# IMU_Board.net
KiCad netlist of a schematic drawn in EAGLE
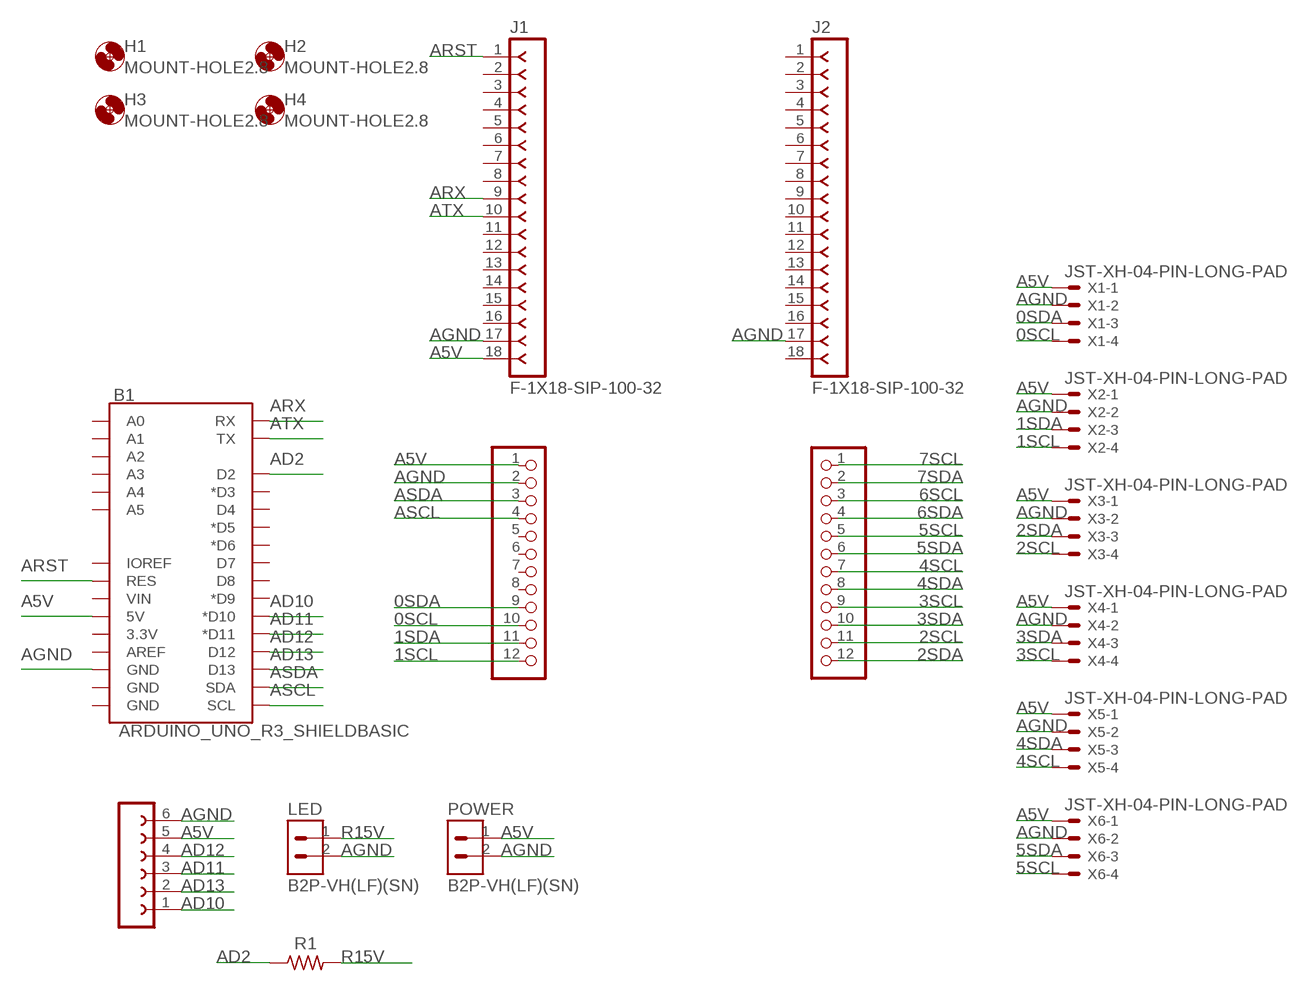
[diagram p0: schematic, sheet 1]

(export (version "E")
  (design (tool "Eeschema 10.0.6"))
  (components
    (comp (ref "B1")
      (value "ARDUINO_UNO_R3_SHIELDBASIC")
      (footprint "eagle-import:UNO_R3_SHIELD")
      (libsource (lib "eagle-import") (part "ARDUINO_UNO_R3_SHIELDBASIC"))
    )
    (comp (ref "H1")
      (value "MOUNT-HOLE2.8")
      (footprint "eagle-import:2,8")
      (libsource (lib "eagle-import") (part "MOUNT-HOLE2.8"))
    )
    (comp (ref "H2")
      (value "MOUNT-HOLE2.8")
      (footprint "eagle-import:2,8")
      (libsource (lib "eagle-import") (part "MOUNT-HOLE2.8"))
    )
    (comp (ref "H3")
      (value "MOUNT-HOLE2.8")
      (footprint "eagle-import:2,8")
      (libsource (lib "eagle-import") (part "MOUNT-HOLE2.8"))
    )
    (comp (ref "H4")
      (value "MOUNT-HOLE2.8")
      (footprint "eagle-import:2,8")
      (libsource (lib "eagle-import") (part "MOUNT-HOLE2.8"))
    )
    (comp (ref "J1")
      (value "F-1X18-SIP-100-32")
      (footprint "eagle-import:SIP-100-18-32")
      (libsource (lib "eagle-import") (part "F-1X18-SIP-100-32"))
    )
    (comp (ref "J2")
      (value "F-1X18-SIP-100-32")
      (footprint "eagle-import:SIP-100-18-32")
      (libsource (lib "eagle-import") (part "F-1X18-SIP-100-32"))
    )
    (comp (ref "JP1")
      (value "HEADER-1X12")
      (footprint "eagle-import:1X12_ROUND")
      (libsource (lib "eagle-import") (part "HEADER-1X12"))
    )
    (comp (ref "JP3")
      (value "HEADER-1X12")
      (footprint "eagle-import:1X12_ROUND")
      (libsource (lib "eagle-import") (part "HEADER-1X12"))
    )
    (comp (ref "LED")
      (value "B2P-VH(LF)(SN)")
      (footprint "eagle-import:HDR-02")
      (fields
        (field (name "DIGIKEY_PART_NUMBER") "455-1639-ND")
        (field (name "MANUFACTURER") "JST Sales America Inc.")
        (field (name "CREATED_BY") "PCBLayout.com")
      )
      (libsource (lib "eagle-import") (part "B2P-VH(LF)(SN)"))
    )
    (comp (ref "POWER")
      (value "B2P-VH(LF)(SN)")
      (footprint "eagle-import:HDR-02")
      (fields
        (field (name "DIGIKEY_PART_NUMBER") "455-1639-ND")
        (field (name "MANUFACTURER") "JST Sales America Inc.")
        (field (name "CREATED_BY") "PCBLayout.com")
      )
      (libsource (lib "eagle-import") (part "B2P-VH(LF)(SN)"))
    )
    (comp (ref "R1")
      (value "R-US_AXIAL-11.7MM-PITCH")
      (footprint "eagle-import:RESAD1176W63L850D250B")
      (libsource (lib "eagle-import") (part "R-USAXIAL-11.7MM-PITCH_"))
    )
    (comp (ref "SD")
      (value "FE06-1")
      (footprint "eagle-import:FE06")
      (libsource (lib "eagle-import") (part "FE06-1"))
    )
    (comp (ref "X1")
      (value "JST-XH-04-PIN-LONG-PAD")
      (footprint "eagle-import:JST-XH-04-PACKAGE-LONG-PAD")
      (libsource (lib "eagle-import") (part "JST-XH-04-PIN-LONG-PAD"))
    )
    (comp (ref "X2")
      (value "JST-XH-04-PIN-LONG-PAD")
      (footprint "eagle-import:JST-XH-04-PACKAGE-LONG-PAD")
      (libsource (lib "eagle-import") (part "JST-XH-04-PIN-LONG-PAD"))
    )
    (comp (ref "X3")
      (value "JST-XH-04-PIN-LONG-PAD")
      (footprint "eagle-import:JST-XH-04-PACKAGE-LONG-PAD")
      (libsource (lib "eagle-import") (part "JST-XH-04-PIN-LONG-PAD"))
    )
    (comp (ref "X4")
      (value "JST-XH-04-PIN-LONG-PAD")
      (footprint "eagle-import:JST-XH-04-PACKAGE-LONG-PAD")
      (libsource (lib "eagle-import") (part "JST-XH-04-PIN-LONG-PAD"))
    )
    (comp (ref "X5")
      (value "JST-XH-04-PIN-LONG-PAD")
      (footprint "eagle-import:JST-XH-04-PACKAGE-LONG-PAD")
      (libsource (lib "eagle-import") (part "JST-XH-04-PIN-LONG-PAD"))
    )
    (comp (ref "X6")
      (value "JST-XH-04-PIN-LONG-PAD")
      (footprint "eagle-import:JST-XH-04-PACKAGE-LONG-PAD")
      (libsource (lib "eagle-import") (part "JST-XH-04-PIN-LONG-PAD"))
    )
  )
  (nets
    (net (code "1") (name "/0SCL") (class "Default")
      (node (ref "JP3") (pin "10") (pinfunction "10_10") (pintype "passive"))
      (node (ref "X1") (pin "4") (pinfunction "S_4") (pintype "passive"))
    )
    (net (code "2") (name "/0SDA") (class "Default")
      (node (ref "JP3") (pin "9") (pinfunction "9_9") (pintype "passive"))
      (node (ref "X1") (pin "3") (pinfunction "S_3") (pintype "passive"))
    )
    (net (code "3") (name "/1SCL") (class "Default")
      (node (ref "JP3") (pin "12") (pinfunction "12_12") (pintype "passive"))
      (node (ref "X2") (pin "4") (pinfunction "S_4") (pintype "passive"))
    )
    (net (code "4") (name "/1SDA") (class "Default")
      (node (ref "JP3") (pin "11") (pinfunction "11_11") (pintype "passive"))
      (node (ref "X2") (pin "3") (pinfunction "S_3") (pintype "passive"))
    )
    (net (code "5") (name "/2SCL") (class "Default")
      (node (ref "JP1") (pin "11") (pinfunction "11_11") (pintype "passive"))
      (node (ref "X3") (pin "4") (pinfunction "S_4") (pintype "passive"))
    )
    (net (code "6") (name "/2SDA") (class "Default")
      (node (ref "JP1") (pin "12") (pinfunction "12_12") (pintype "passive"))
      (node (ref "X3") (pin "3") (pinfunction "S_3") (pintype "passive"))
    )
    (net (code "7") (name "/3SCL") (class "Default")
      (node (ref "JP1") (pin "9") (pinfunction "9_9") (pintype "passive"))
      (node (ref "X4") (pin "4") (pinfunction "S_4") (pintype "passive"))
    )
    (net (code "8") (name "/3SDA") (class "Default")
      (node (ref "JP1") (pin "10") (pinfunction "10_10") (pintype "passive"))
      (node (ref "X4") (pin "3") (pinfunction "S_3") (pintype "passive"))
    )
    (net (code "9") (name "/4SCL") (class "Default")
      (node (ref "JP1") (pin "7") (pinfunction "7_7") (pintype "passive"))
      (node (ref "X5") (pin "4") (pinfunction "S_4") (pintype "passive"))
    )
    (net (code "10") (name "/4SDA") (class "Default")
      (node (ref "JP1") (pin "8") (pinfunction "8_8") (pintype "passive"))
      (node (ref "X5") (pin "3") (pinfunction "S_3") (pintype "passive"))
    )
    (net (code "11") (name "/5SCL") (class "Default")
      (node (ref "JP1") (pin "5") (pinfunction "5_5") (pintype "passive"))
      (node (ref "X6") (pin "4") (pinfunction "S_4") (pintype "passive"))
    )
    (net (code "12") (name "/5SDA") (class "Default")
      (node (ref "JP1") (pin "6") (pinfunction "6_6") (pintype "passive"))
      (node (ref "X6") (pin "3") (pinfunction "S_3") (pintype "passive"))
    )
    (net (code "13") (name "/6SCL") (class "Default")
      (node (ref "JP1") (pin "3") (pinfunction "3_3") (pintype "passive"))
    )
    (net (code "14") (name "/6SDA") (class "Default")
      (node (ref "JP1") (pin "4") (pinfunction "4_4") (pintype "passive"))
    )
    (net (code "15") (name "/7SCL") (class "Default")
      (node (ref "JP1") (pin "1") (pinfunction "1_1") (pintype "passive"))
    )
    (net (code "16") (name "/7SDA") (class "Default")
      (node (ref "JP1") (pin "2") (pinfunction "2_2") (pintype "passive"))
    )
    (net (code "17") (name "/A5V") (class "Default")
      (node (ref "B1") (pin "5V") (pinfunction "5V_5V") (pintype "bidirectional"))
      (node (ref "J1") (pin "18") (pinfunction "18_18") (pintype "passive"))
      (node (ref "JP3") (pin "1") (pinfunction "1_1") (pintype "passive"))
      (node (ref "POWER") (pin "1") (pinfunction "1_1") (pintype "passive"))
      (node (ref "SD") (pin "5") (pinfunction "5_5") (pintype "passive"))
      (node (ref "X1") (pin "1") (pinfunction "S_1") (pintype "passive"))
      (node (ref "X2") (pin "1") (pinfunction "S_1") (pintype "passive"))
      (node (ref "X3") (pin "1") (pinfunction "S_1") (pintype "passive"))
      (node (ref "X4") (pin "1") (pinfunction "S_1") (pintype "passive"))
      (node (ref "X5") (pin "1") (pinfunction "S_1") (pintype "passive"))
      (node (ref "X6") (pin "1") (pinfunction "S_1") (pintype "passive"))
    )
    (net (code "18") (name "/AD2") (class "Default")
      (node (ref "B1") (pin "D2") (pinfunction "D2_D2") (pintype "bidirectional"))
      (node (ref "R1") (pin "1") (pinfunction "1_1") (pintype "passive"))
    )
    (net (code "19") (name "/AD10") (class "Default")
      (node (ref "B1") (pin "D10") (pinfunction "*D10_D10") (pintype "bidirectional"))
      (node (ref "SD") (pin "1") (pinfunction "1_1") (pintype "passive"))
    )
    (net (code "20") (name "/AD11") (class "Default")
      (node (ref "B1") (pin "D11") (pinfunction "*D11_D11") (pintype "bidirectional"))
      (node (ref "SD") (pin "3") (pinfunction "3_3") (pintype "passive"))
    )
    (net (code "21") (name "/AD12") (class "Default")
      (node (ref "B1") (pin "D12") (pinfunction "D12_D12") (pintype "bidirectional"))
      (node (ref "SD") (pin "4") (pinfunction "4_4") (pintype "passive"))
    )
    (net (code "22") (name "/AD13") (class "Default")
      (node (ref "B1") (pin "D13") (pinfunction "D13_D13") (pintype "bidirectional"))
      (node (ref "SD") (pin "2") (pinfunction "2_2") (pintype "passive"))
    )
    (net (code "23") (name "/AGND") (class "Default")
      (node (ref "B1") (pin "GND@2") (pinfunction "GND_GND@2") (pintype "bidirectional"))
      (node (ref "J1") (pin "17") (pinfunction "17_17") (pintype "passive"))
      (node (ref "J2") (pin "17") (pinfunction "17_17") (pintype "passive"))
      (node (ref "JP3") (pin "2") (pinfunction "2_2") (pintype "passive"))
      (node (ref "LED") (pin "2") (pinfunction "2_2") (pintype "passive"))
      (node (ref "POWER") (pin "2") (pinfunction "2_2") (pintype "passive"))
      (node (ref "SD") (pin "6") (pinfunction "6_6") (pintype "passive"))
      (node (ref "X1") (pin "2") (pinfunction "S_2") (pintype "passive"))
      (node (ref "X2") (pin "2") (pinfunction "S_2") (pintype "passive"))
      (node (ref "X3") (pin "2") (pinfunction "S_2") (pintype "passive"))
      (node (ref "X4") (pin "2") (pinfunction "S_2") (pintype "passive"))
      (node (ref "X5") (pin "2") (pinfunction "S_2") (pintype "passive"))
      (node (ref "X6") (pin "2") (pinfunction "S_2") (pintype "passive"))
    )
    (net (code "24") (name "/ARST") (class "Default")
      (node (ref "B1") (pin "RES") (pinfunction "RES_RES") (pintype "bidirectional"))
      (node (ref "J1") (pin "1") (pinfunction "1_1") (pintype "passive"))
    )
    (net (code "25") (name "/ARX") (class "Default")
      (node (ref "B1") (pin "RX") (pinfunction "RX_RX") (pintype "bidirectional"))
      (node (ref "J1") (pin "9") (pinfunction "9_9") (pintype "passive"))
    )
    (net (code "26") (name "/ASCL") (class "Default")
      (node (ref "B1") (pin "SCL") (pinfunction "SCL_SCL") (pintype "bidirectional"))
      (node (ref "JP3") (pin "4") (pinfunction "4_4") (pintype "passive"))
    )
    (net (code "27") (name "/ASDA") (class "Default")
      (node (ref "B1") (pin "SDA") (pinfunction "SDA_SDA") (pintype "bidirectional"))
      (node (ref "JP3") (pin "3") (pinfunction "3_3") (pintype "passive"))
    )
    (net (code "28") (name "/ATX") (class "Default")
      (node (ref "B1") (pin "TX") (pinfunction "TX_TX") (pintype "bidirectional"))
      (node (ref "J1") (pin "10") (pinfunction "10_10") (pintype "passive"))
    )
    (net (code "29") (name "/R15V") (class "Default")
      (node (ref "LED") (pin "1") (pinfunction "1_1") (pintype "passive"))
      (node (ref "R1") (pin "2") (pinfunction "2_2") (pintype "passive"))
    )
    (net (code "30") (name "unconnected-(B1-*D3-PadD3)") (class "Default")
      (node (ref "B1") (pin "D3") (pinfunction "*D3_D3") (pintype "bidirectional"))
    )
    (net (code "31") (name "unconnected-(B1-*D5-PadD5)") (class "Default")
      (node (ref "B1") (pin "D5") (pinfunction "*D5_D5") (pintype "bidirectional"))
    )
    (net (code "32") (name "unconnected-(B1-*D6-PadD6)") (class "Default")
      (node (ref "B1") (pin "D6") (pinfunction "*D6_D6") (pintype "bidirectional"))
    )
    (net (code "33") (name "unconnected-(B1-*D9-PadD9)") (class "Default")
      (node (ref "B1") (pin "D9") (pinfunction "*D9_D9") (pintype "bidirectional"))
    )
    (net (code "34") (name "unconnected-(B1-GND-PadGND@0)") (class "Default")
      (node (ref "B1") (pin "GND@0") (pinfunction "GND_GND@0") (pintype "bidirectional"))
    )
    (net (code "35") (name "unconnected-(B1-GND-PadGND@1)") (class "Default")
      (node (ref "B1") (pin "GND@1") (pinfunction "GND_GND@1") (pintype "bidirectional"))
    )
    (net (code "36") (name "unconnected-(B1-Pad3.3V)") (class "Default")
      (node (ref "B1") (pin "3.3V") (pinfunction "3.3V_3.3V") (pintype "bidirectional"))
    )
    (net (code "37") (name "unconnected-(B1-PadA0)") (class "Default")
      (node (ref "B1") (pin "A0") (pinfunction "A0_A0") (pintype "bidirectional"))
    )
    (net (code "38") (name "unconnected-(B1-PadA1)") (class "Default")
      (node (ref "B1") (pin "A1") (pinfunction "A1_A1") (pintype "bidirectional"))
    )
    (net (code "39") (name "unconnected-(B1-PadA2)") (class "Default")
      (node (ref "B1") (pin "A2") (pinfunction "A2_A2") (pintype "bidirectional"))
    )
    (net (code "40") (name "unconnected-(B1-PadA3)") (class "Default")
      (node (ref "B1") (pin "A3") (pinfunction "A3_A3") (pintype "bidirectional"))
    )
    (net (code "41") (name "unconnected-(B1-PadA4)") (class "Default")
      (node (ref "B1") (pin "A4") (pinfunction "A4_A4") (pintype "bidirectional"))
    )
    (net (code "42") (name "unconnected-(B1-PadA5)") (class "Default")
      (node (ref "B1") (pin "A5") (pinfunction "A5_A5") (pintype "bidirectional"))
    )
    (net (code "43") (name "unconnected-(B1-PadAREF)") (class "Default")
      (node (ref "B1") (pin "AREF") (pinfunction "AREF_AREF") (pintype "bidirectional"))
    )
    (net (code "44") (name "unconnected-(B1-PadD4)") (class "Default")
      (node (ref "B1") (pin "D4") (pinfunction "D4_D4") (pintype "bidirectional"))
    )
    (net (code "45") (name "unconnected-(B1-PadD7)") (class "Default")
      (node (ref "B1") (pin "D7") (pinfunction "D7_D7") (pintype "bidirectional"))
    )
    (net (code "46") (name "unconnected-(B1-PadD8)") (class "Default")
      (node (ref "B1") (pin "D8") (pinfunction "D8_D8") (pintype "bidirectional"))
    )
    (net (code "47") (name "unconnected-(B1-PadIOREF)") (class "Default")
      (node (ref "B1") (pin "IOREF") (pinfunction "IOREF_IOREF") (pintype "bidirectional"))
    )
    (net (code "48") (name "unconnected-(B1-PadVIN)") (class "Default")
      (node (ref "B1") (pin "VIN") (pinfunction "VIN_VIN") (pintype "bidirectional"))
    )
    (net (code "49") (name "unconnected-(J1-Pad2)") (class "Default")
      (node (ref "J1") (pin "2") (pinfunction "2_2") (pintype "passive"))
    )
    (net (code "50") (name "unconnected-(J1-Pad3)") (class "Default")
      (node (ref "J1") (pin "3") (pinfunction "3_3") (pintype "passive"))
    )
    (net (code "51") (name "unconnected-(J1-Pad4)") (class "Default")
      (node (ref "J1") (pin "4") (pinfunction "4_4") (pintype "passive"))
    )
    (net (code "52") (name "unconnected-(J1-Pad5)") (class "Default")
      (node (ref "J1") (pin "5") (pinfunction "5_5") (pintype "passive"))
    )
    (net (code "53") (name "unconnected-(J1-Pad6)") (class "Default")
      (node (ref "J1") (pin "6") (pinfunction "6_6") (pintype "passive"))
    )
    (net (code "54") (name "unconnected-(J1-Pad7)") (class "Default")
      (node (ref "J1") (pin "7") (pinfunction "7_7") (pintype "passive"))
    )
    (net (code "55") (name "unconnected-(J1-Pad8)") (class "Default")
      (node (ref "J1") (pin "8") (pinfunction "8_8") (pintype "passive"))
    )
    (net (code "56") (name "unconnected-(J1-Pad11)") (class "Default")
      (node (ref "J1") (pin "11") (pinfunction "11_11") (pintype "passive"))
    )
    (net (code "57") (name "unconnected-(J1-Pad12)") (class "Default")
      (node (ref "J1") (pin "12") (pinfunction "12_12") (pintype "passive"))
    )
    (net (code "58") (name "unconnected-(J1-Pad13)") (class "Default")
      (node (ref "J1") (pin "13") (pinfunction "13_13") (pintype "passive"))
    )
    (net (code "59") (name "unconnected-(J1-Pad14)") (class "Default")
      (node (ref "J1") (pin "14") (pinfunction "14_14") (pintype "passive"))
    )
    (net (code "60") (name "unconnected-(J1-Pad15)") (class "Default")
      (node (ref "J1") (pin "15") (pinfunction "15_15") (pintype "passive"))
    )
    (net (code "61") (name "unconnected-(J1-Pad16)") (class "Default")
      (node (ref "J1") (pin "16") (pinfunction "16_16") (pintype "passive"))
    )
    (net (code "62") (name "unconnected-(J2-Pad1)") (class "Default")
      (node (ref "J2") (pin "1") (pinfunction "1_1") (pintype "passive"))
    )
    (net (code "63") (name "unconnected-(J2-Pad2)") (class "Default")
      (node (ref "J2") (pin "2") (pinfunction "2_2") (pintype "passive"))
    )
    (net (code "64") (name "unconnected-(J2-Pad3)") (class "Default")
      (node (ref "J2") (pin "3") (pinfunction "3_3") (pintype "passive"))
    )
    (net (code "65") (name "unconnected-(J2-Pad4)") (class "Default")
      (node (ref "J2") (pin "4") (pinfunction "4_4") (pintype "passive"))
    )
    (net (code "66") (name "unconnected-(J2-Pad5)") (class "Default")
      (node (ref "J2") (pin "5") (pinfunction "5_5") (pintype "passive"))
    )
    (net (code "67") (name "unconnected-(J2-Pad6)") (class "Default")
      (node (ref "J2") (pin "6") (pinfunction "6_6") (pintype "passive"))
    )
    (net (code "68") (name "unconnected-(J2-Pad7)") (class "Default")
      (node (ref "J2") (pin "7") (pinfunction "7_7") (pintype "passive"))
    )
    (net (code "69") (name "unconnected-(J2-Pad8)") (class "Default")
      (node (ref "J2") (pin "8") (pinfunction "8_8") (pintype "passive"))
    )
    (net (code "70") (name "unconnected-(J2-Pad9)") (class "Default")
      (node (ref "J2") (pin "9") (pinfunction "9_9") (pintype "passive"))
    )
    (net (code "71") (name "unconnected-(J2-Pad10)") (class "Default")
      (node (ref "J2") (pin "10") (pinfunction "10_10") (pintype "passive"))
    )
    (net (code "72") (name "unconnected-(J2-Pad11)") (class "Default")
      (node (ref "J2") (pin "11") (pinfunction "11_11") (pintype "passive"))
    )
    (net (code "73") (name "unconnected-(J2-Pad12)") (class "Default")
      (node (ref "J2") (pin "12") (pinfunction "12_12") (pintype "passive"))
    )
    (net (code "74") (name "unconnected-(J2-Pad13)") (class "Default")
      (node (ref "J2") (pin "13") (pinfunction "13_13") (pintype "passive"))
    )
    (net (code "75") (name "unconnected-(J2-Pad14)") (class "Default")
      (node (ref "J2") (pin "14") (pinfunction "14_14") (pintype "passive"))
    )
    (net (code "76") (name "unconnected-(J2-Pad15)") (class "Default")
      (node (ref "J2") (pin "15") (pinfunction "15_15") (pintype "passive"))
    )
    (net (code "77") (name "unconnected-(J2-Pad16)") (class "Default")
      (node (ref "J2") (pin "16") (pinfunction "16_16") (pintype "passive"))
    )
    (net (code "78") (name "unconnected-(J2-Pad18)") (class "Default")
      (node (ref "J2") (pin "18") (pinfunction "18_18") (pintype "passive"))
    )
    (net (code "79") (name "unconnected-(JP3-Pad5)") (class "Default")
      (node (ref "JP3") (pin "5") (pinfunction "5_5") (pintype "passive"))
    )
    (net (code "80") (name "unconnected-(JP3-Pad6)") (class "Default")
      (node (ref "JP3") (pin "6") (pinfunction "6_6") (pintype "passive"))
    )
    (net (code "81") (name "unconnected-(JP3-Pad7)") (class "Default")
      (node (ref "JP3") (pin "7") (pinfunction "7_7") (pintype "passive"))
    )
    (net (code "82") (name "unconnected-(JP3-Pad8)") (class "Default")
      (node (ref "JP3") (pin "8") (pinfunction "8_8") (pintype "passive"))
    )
  )
)
